# current_sense.net
KiCad netlist of a schematic drawn in Altium Designer
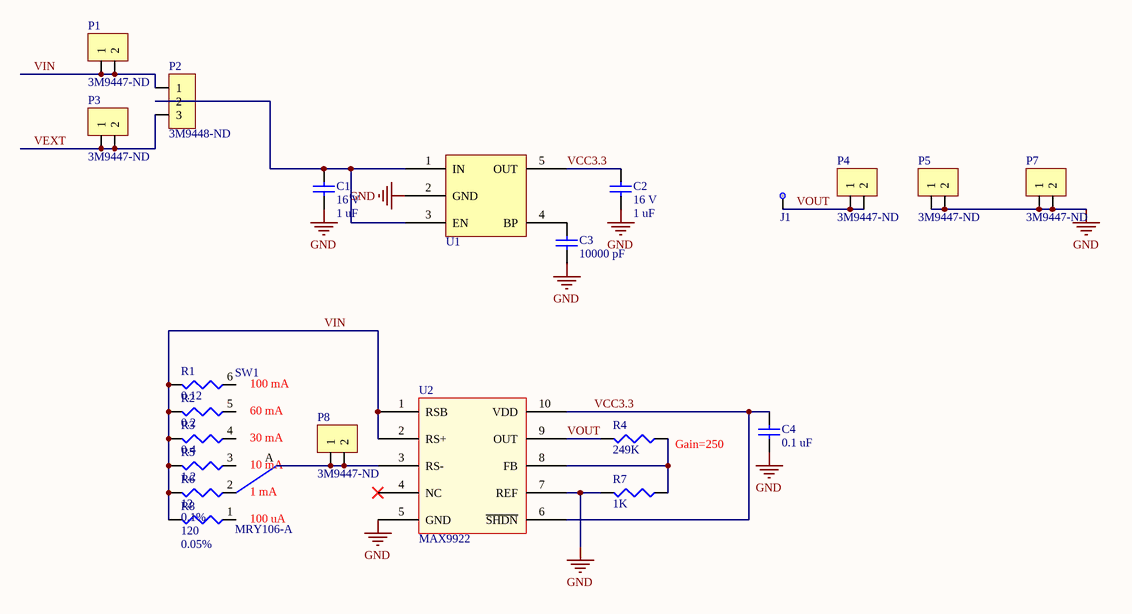
[diagram p0: current_sense.SchDoc]

(export (version "E")
  (design (tool "Eeschema 10.0.6"))
  (components
    (comp (ref "C1")
      (value "1 uF")
      (footprint "0603")
      (description "Ceramic capacitor, 1 uF, 16 V, 0603 package")
      (fields
        (field (name "TOLERANCE") "10%")
        (field (name "VOLTAGE RATED") "16 V")
        (field (name "Comment") "Ceramic capacitor")
      )
      (libsource (lib "rlc") (part "C_1u_16V_0603_ceramic"))
    )
    (comp (ref "C2")
      (value "1 uF")
      (footprint "0603")
      (description "Ceramic capacitor, 1 uF, 16 V, 0603 package")
      (fields
        (field (name "TOLERANCE") "10%")
        (field (name "VOLTAGE RATED") "16 V")
        (field (name "Comment") "Ceramic capacitor")
      )
      (libsource (lib "rlc") (part "C_1u_16V_0603_ceramic"))
    )
    (comp (ref "C3")
      (value "10000 pF")
      (footprint "0603")
      (description "Ceramic capacitor, 10000 pF, 0603 package")
      (fields (field (name "TOLERANCE") "10%") (field (name "Comment") "Ceramic capacitor"))
      (libsource (lib "rlc") (part "C_10000p_25V_0603_ceramic"))
    )
    (comp (ref "C4")
      (value "0.1 uF")
      (footprint "0603")
      (description "Ceramic capacitor, 0.1 uF, 0603 package")
      (fields (field (name "TOLERANCE") "10%") (field (name "Comment") "Ceramic capacitor"))
      (libsource (lib "rlc") (part "C_0.1u_25V_0603_ceramic"))
    )
    (comp (ref "J1")
      (value "5004")
      (footprint "TestPoint")
      (description "TEST POINT PC MINI .040\"D YELLOW")
      (libsource (lib "connectors") (part "TestPoint"))
    )
    (comp (ref "P1")
      (value "1 x 2 header")
      (footprint "1x2 header")
      (description "100 mils standard header")
      (fields (field (name "SUPPLIER PART NUMBER 1") "3M9447-ND"))
      (libsource (lib "connectors") (part "1 x 2 header"))
    )
    (comp (ref "P2")
      (value "1 x 3 header")
      (footprint "1x3 header")
      (description "100 mils standard header")
      (fields (field (name "SUPPLIER PART NUMBER 1") "3M9448-ND"))
      (libsource (lib "connectors") (part "1 x 3 header"))
    )
    (comp (ref "P3")
      (value "1 x 2 header")
      (footprint "1x2 header")
      (description "100 mils standard header")
      (fields (field (name "SUPPLIER PART NUMBER 1") "3M9447-ND"))
      (libsource (lib "connectors") (part "1 x 2 header"))
    )
    (comp (ref "P4")
      (value "1 x 2 header")
      (footprint "1x2 header")
      (description "100 mils standard header")
      (fields (field (name "SUPPLIER PART NUMBER 1") "3M9447-ND"))
      (libsource (lib "connectors") (part "1 x 2 header"))
    )
    (comp (ref "P5")
      (value "1 x 2 header")
      (footprint "1x2 header")
      (description "100 mils standard header")
      (fields (field (name "SUPPLIER PART NUMBER 1") "3M9447-ND"))
      (libsource (lib "connectors") (part "1 x 2 header"))
    )
    (comp (ref "P7")
      (value "1 x 2 header")
      (footprint "1x2 header")
      (description "100 mils standard header")
      (fields (field (name "SUPPLIER PART NUMBER 1") "3M9447-ND"))
      (libsource (lib "connectors") (part "1 x 2 header"))
    )
    (comp (ref "P8")
      (value "1 x 2 header")
      (footprint "1x2 header")
      (description "100 mils standard header")
      (fields (field (name "SUPPLIER PART NUMBER 1") "3M9447-ND"))
      (libsource (lib "connectors") (part "1 x 2 header"))
    )
    (comp (ref "R1")
      (value "0.12")
      (footprint "1206")
      (description "Chip resistor, 0.12, 1206 package, current sense")
      (fields (field (name "TOLERANCE") "1%") (field (name "POWER") "0.5 W"))
      (libsource (lib "rlc") (part "R_0.12_1206_1%"))
    )
    (comp (ref "R2")
      (value "0.2")
      (footprint "1206")
      (description "Chip resistor, 0.2, 1206 package, current sense")
      (fields (field (name "TOLERANCE") "1%") (field (name "POWER") "0.5 W"))
      (libsource (lib "rlc") (part "R_0.2_1206_1%"))
    )
    (comp (ref "R3")
      (value "0.4")
      (footprint "1206")
      (description "Chip resistor, 0.4, 1206 package, current sense")
      (fields (field (name "TOLERANCE") "1%") (field (name "POWER") "0.25 W"))
      (libsource (lib "rlc") (part "R_0.4_1206_1%"))
    )
    (comp (ref "R4")
      (value "249K")
      (footprint "0603")
      (description "Chip resistor, 249 K, 0603 package")
      (fields (field (name "TOLERANCE") "0.1%") (field (name "POWER") "1/10 W"))
      (libsource (lib "rlc") (part "R_249K_0603_0.1%"))
    )
    (comp (ref "R5")
      (value "1.2")
      (footprint "0805")
      (description "Chip resistor, 1.2, 0805 package, current sense")
      (fields (field (name "TOLERANCE") "1%") (field (name "POWER") "0.333 W"))
      (libsource (lib "rlc") (part "R_1.2_0805_1%"))
    )
    (comp (ref "R6")
      (value "12")
      (footprint "0805")
      (description "Chip resistor, 12, 0805 package, current sense")
      (fields
        (field (name "POWER") "0.1 W")
        (field (name "TOLERANCE") "0.1%")
        (field (name "Comment") "Chip resistor")
      )
      (libsource (lib "rlc") (part "R_12_0805"))
    )
    (comp (ref "R7")
      (value "1K")
      (footprint "0603")
      (description "Chip resistor, 1 K, 0603 package")
      (fields (field (name "TOLERANCE") "0.1%") (field (name "POWER") "1/10 W"))
      (libsource (lib "rlc") (part "R_1K_0603_0.1%"))
    )
    (comp (ref "R8")
      (value "120")
      (footprint "0805")
      (description "Chip resistor, 120, 0805 package, current sense")
      (fields
        (field (name "POWER") "0.125 W")
        (field (name "TOLERANCE") "0.05%")
        (field (name "Comment") "Chip resistor")
      )
      (libsource (lib "rlc") (part "R_120_0805"))
    )
    (comp (ref "SW1")
      (value "MRY106-A")
      (footprint "MRY switch")
      (description "SW ROTARY SP BLK KNOB 125V")
      (libsource (lib "current_sense") (part "MRY106-A"))
    )
    (comp (ref "U1")
      (value "LP3985")
      (footprint "SOT23-5")
      (description "LP3985 Micropower, 150-mA Low-Noise Ultra Low-Dropout CMOS Voltage Regulator")
      (libsource (lib "voltage_regulators") (part "LP3985"))
    )
    (comp (ref "U2")
      (value "MAX9922")
      (footprint "10umax")
      (description "ultra-precision, high-side current-sense amplifier")
      (libsource (lib "amplifier") (part "MAX9922"))
    )
  )
  (nets
    (net (code "1") (name "/VCC3.3") (class "Default")
      (node (ref "C2") (pin "1") (pintype "passive"))
      (node (ref "C4") (pin "1") (pintype "passive"))
      (node (ref "U1") (pin "5") (pinfunction "OUT_5") (pintype "passive"))
      (node (ref "U2") (pin "10") (pinfunction "VDD_10") (pintype "passive"))
      (node (ref "U2") (pin "6") (pinfunction "~{SHDN}_6") (pintype "passive"))
    )
    (net (code "2") (name "/VEXT") (class "Default")
      (node (ref "P2") (pin "3") (pinfunction "3_3") (pintype "passive"))
      (node (ref "P3") (pin "1") (pinfunction "1_1") (pintype "passive"))
      (node (ref "P3") (pin "2") (pinfunction "2_2") (pintype "passive"))
    )
    (net (code "3") (name "/VIN") (class "Default")
      (node (ref "P1") (pin "1") (pinfunction "1_1") (pintype "passive"))
      (node (ref "P1") (pin "2") (pinfunction "2_2") (pintype "passive"))
      (node (ref "P2") (pin "1") (pinfunction "1_1") (pintype "passive"))
      (node (ref "R1") (pin "1") (pintype "passive"))
      (node (ref "R2") (pin "1") (pintype "passive"))
      (node (ref "R3") (pin "1") (pintype "passive"))
      (node (ref "R5") (pin "1") (pintype "passive"))
      (node (ref "R6") (pin "1") (pintype "passive"))
      (node (ref "R8") (pin "1") (pintype "passive"))
      (node (ref "U2") (pin "1") (pinfunction "RSB_1") (pintype "passive"))
      (node (ref "U2") (pin "2") (pinfunction "RS+_2") (pintype "passive"))
    )
    (net (code "4") (name "/VOUT") (class "Default")
      (node (ref "J1") (pin "1") (pinfunction "TB_1") (pintype "passive"))
      (node (ref "P4") (pin "1") (pinfunction "1_1") (pintype "passive"))
      (node (ref "P4") (pin "2") (pinfunction "2_2") (pintype "passive"))
      (node (ref "R4") (pin "1") (pintype "passive"))
      (node (ref "U2") (pin "9") (pinfunction "OUT_9") (pintype "passive"))
    )
    (net (code "5") (name "GND") (class "Default")
      (node (ref "C1") (pin "2") (pintype "passive"))
      (node (ref "C2") (pin "2") (pintype "passive"))
      (node (ref "C3") (pin "2") (pintype "passive"))
      (node (ref "C4") (pin "2") (pintype "passive"))
      (node (ref "P5") (pin "1") (pinfunction "1_1") (pintype "passive"))
      (node (ref "P5") (pin "2") (pinfunction "2_2") (pintype "passive"))
      (node (ref "P7") (pin "1") (pinfunction "1_1") (pintype "passive"))
      (node (ref "P7") (pin "2") (pinfunction "2_2") (pintype "passive"))
      (node (ref "R7") (pin "1") (pintype "passive"))
      (node (ref "U1") (pin "2") (pinfunction "GND_2") (pintype "passive"))
      (node (ref "U2") (pin "5") (pinfunction "GND_5") (pintype "passive"))
      (node (ref "U2") (pin "7") (pinfunction "REF_7") (pintype "passive"))
    )
    (net (code "6") (name "Net-(R1-Pad2)") (class "Default")
      (node (ref "R1") (pin "2") (pintype "passive"))
      (node (ref "SW1") (pin "6") (pinfunction "6_6") (pintype "passive"))
    )
    (net (code "7") (name "Net-(R2-Pad2)") (class "Default")
      (node (ref "R2") (pin "2") (pintype "passive"))
      (node (ref "SW1") (pin "5") (pinfunction "5_5") (pintype "passive"))
    )
    (net (code "8") (name "Net-(R3-Pad2)") (class "Default")
      (node (ref "R3") (pin "2") (pintype "passive"))
      (node (ref "SW1") (pin "4") (pinfunction "4_4") (pintype "passive"))
    )
    (net (code "9") (name "Net-(R5-Pad2)") (class "Default")
      (node (ref "R5") (pin "2") (pintype "passive"))
      (node (ref "SW1") (pin "3") (pinfunction "3_3") (pintype "passive"))
    )
    (net (code "10") (name "Net-(R6-Pad2)") (class "Default")
      (node (ref "R6") (pin "2") (pintype "passive"))
      (node (ref "SW1") (pin "2") (pinfunction "2_2") (pintype "passive"))
    )
    (net (code "11") (name "Net-(R8-Pad2)") (class "Default")
      (node (ref "R8") (pin "2") (pintype "passive"))
      (node (ref "SW1") (pin "1") (pinfunction "1_1") (pintype "passive"))
    )
    (net (code "12") (name "Net-(U1-BP)") (class "Default")
      (node (ref "C3") (pin "1") (pintype "passive"))
      (node (ref "U1") (pin "4") (pinfunction "BP_4") (pintype "passive"))
    )
    (net (code "13") (name "Net-(U1-EN)") (class "Default")
      (node (ref "C1") (pin "1") (pintype "passive"))
      (node (ref "P2") (pin "2") (pinfunction "2_2") (pintype "passive"))
      (node (ref "U1") (pin "1") (pinfunction "IN_1") (pintype "passive"))
      (node (ref "U1") (pin "3") (pinfunction "EN_3") (pintype "passive"))
    )
    (net (code "14") (name "Net-(U2-FB)") (class "Default")
      (node (ref "R4") (pin "2") (pintype "passive"))
      (node (ref "R7") (pin "2") (pintype "passive"))
      (node (ref "U2") (pin "8") (pinfunction "FB_8") (pintype "passive"))
    )
    (net (code "15") (name "Net-(U2-RS-)") (class "Default")
      (node (ref "P8") (pin "1") (pinfunction "1_1") (pintype "passive"))
      (node (ref "P8") (pin "2") (pinfunction "2_2") (pintype "passive"))
      (node (ref "SW1") (pin "A") (pinfunction "A_A") (pintype "passive"))
      (node (ref "U2") (pin "3") (pinfunction "RS-_3") (pintype "passive"))
    )
    (net (code "16") (name "unconnected-(U2-NC-Pad4)") (class "Default")
      (node (ref "U2") (pin "4") (pinfunction "NC_4") (pintype "passive+no_connect"))
    )
  )
)
